# board.net
KiCad netlist of a schematic drawn in EAGLE
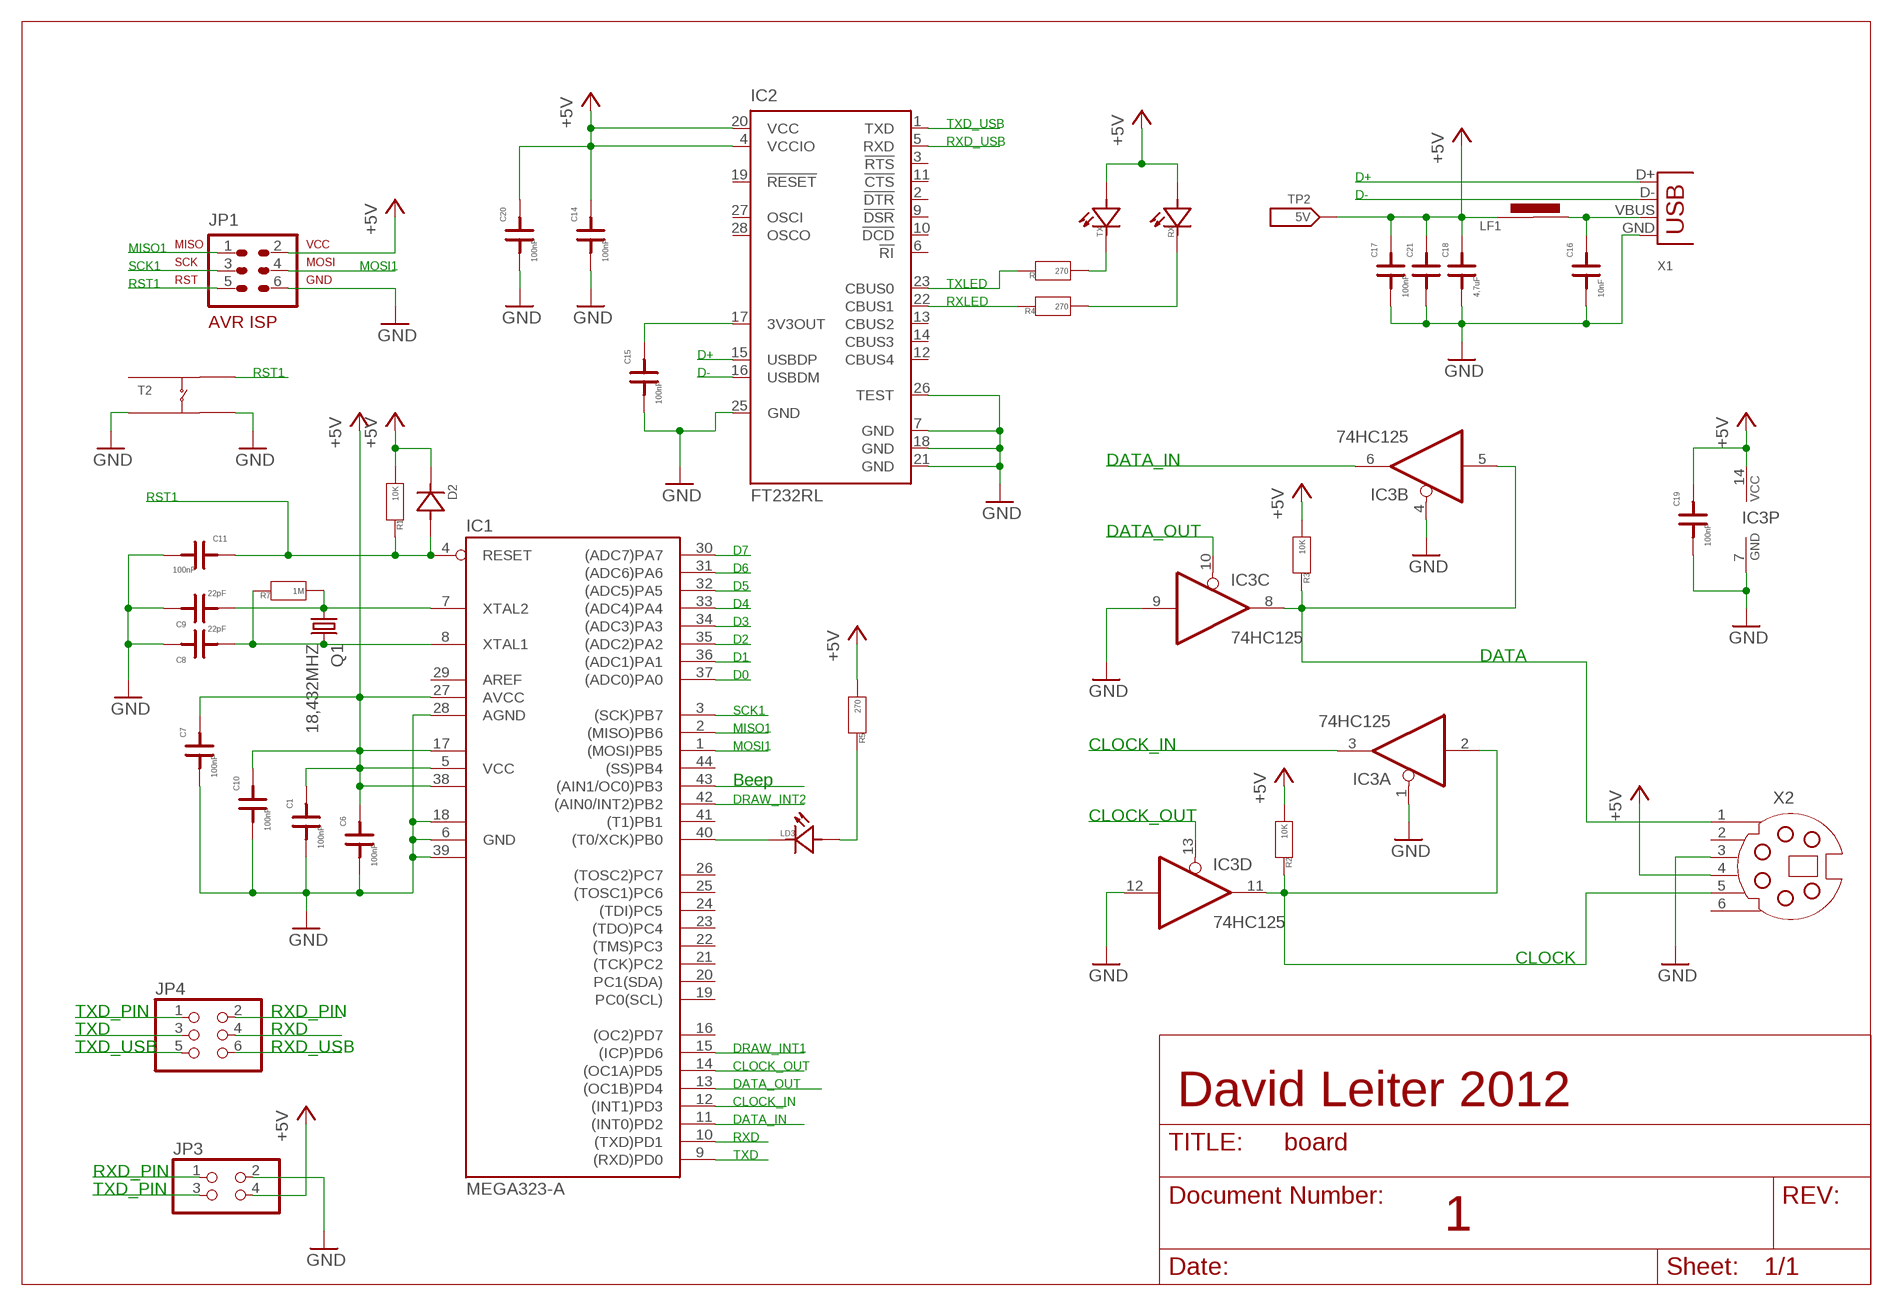
[diagram p0: schematic, sheet 1, part 1 of 2]
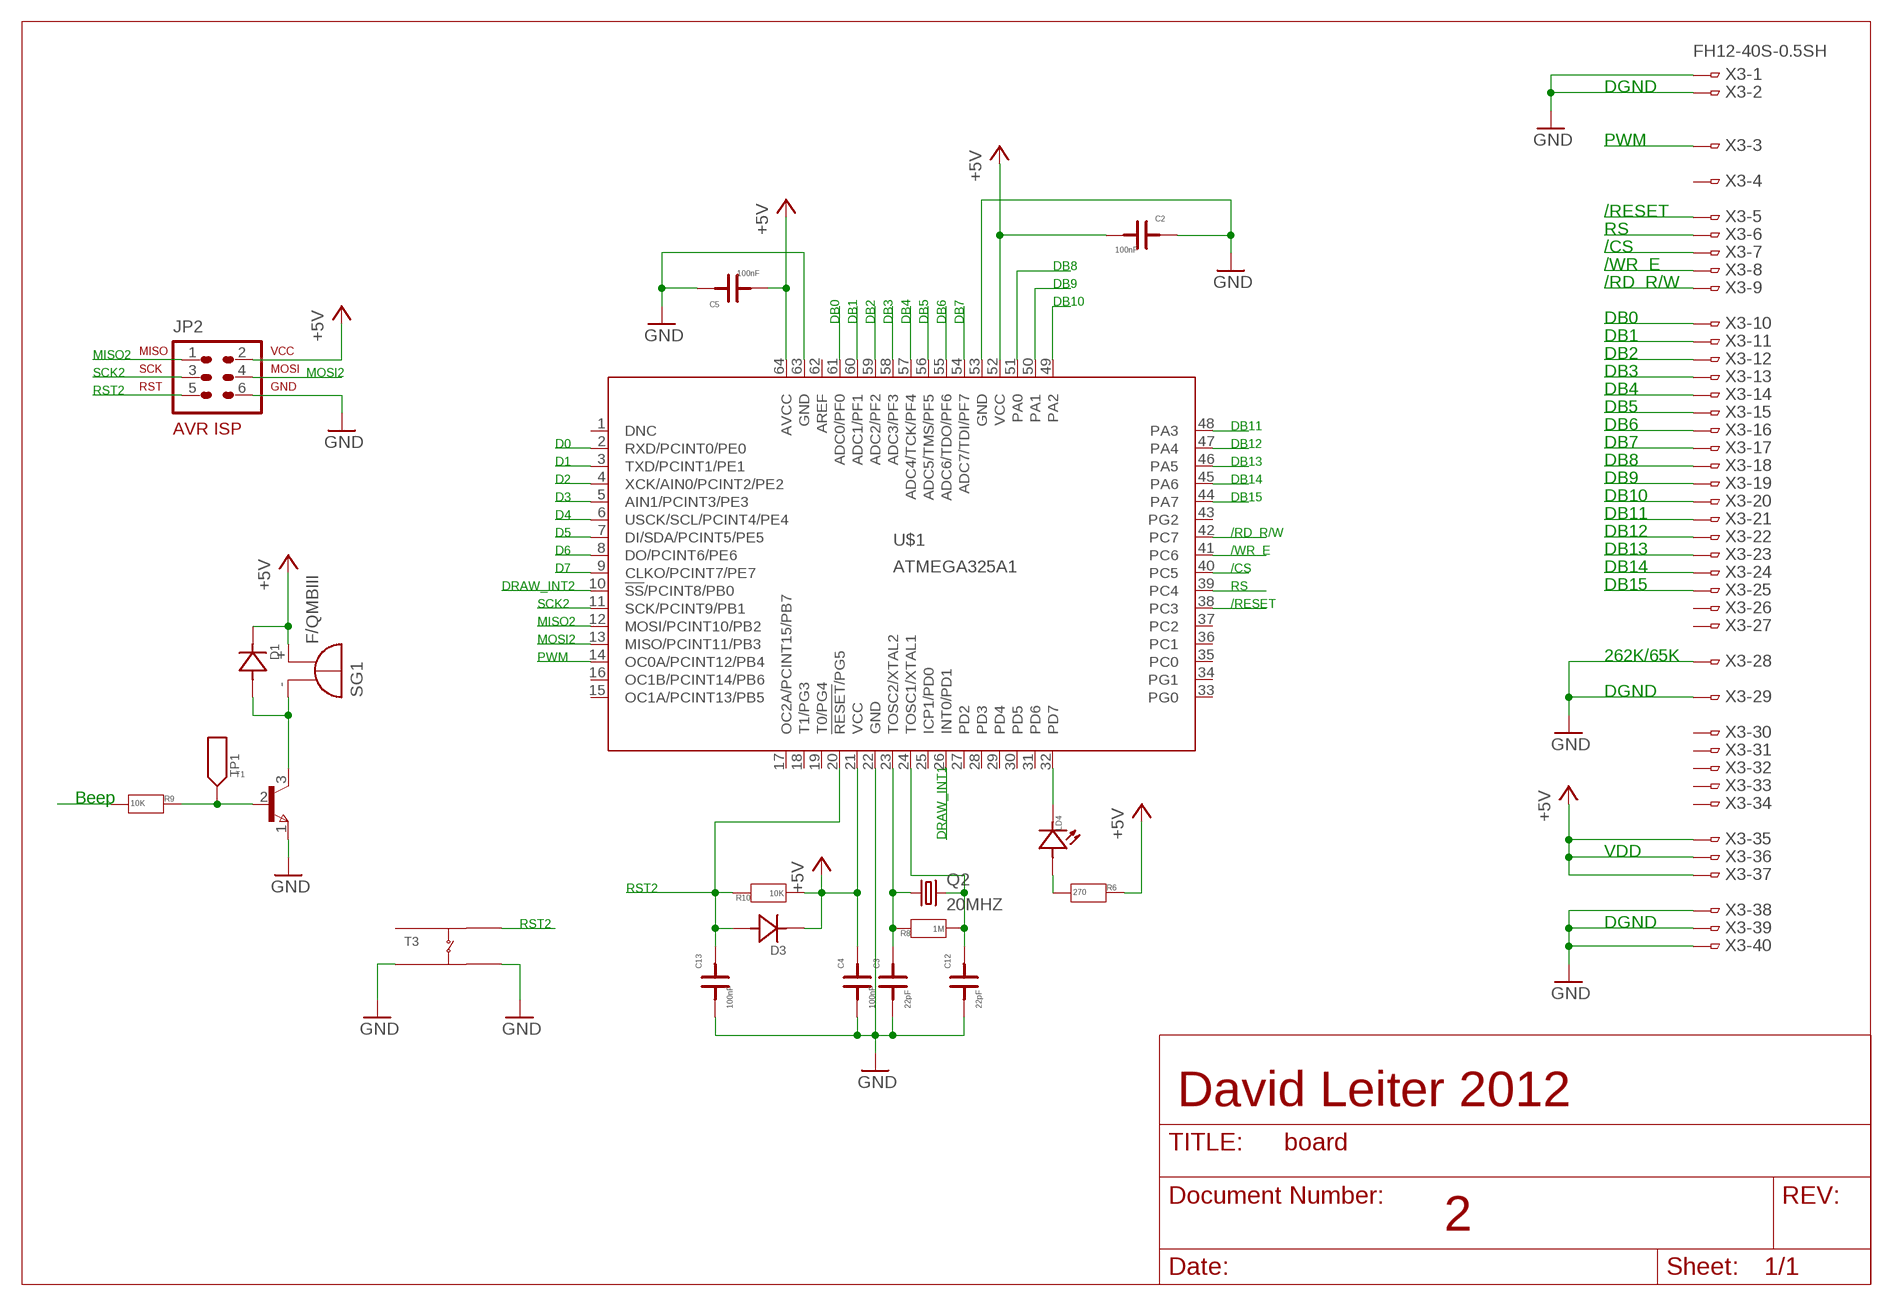
[diagram p1: schematic, sheet 1, part 2 of 2]

(export (version "E")
  (design (tool "Eeschema 10.0.6"))
  (components
    (comp (ref "C1")
      (value "100nF")
      (footprint "eagle-import:0805F")
      (libsource (lib "eagle-import") (part "C1"))
    )
    (comp (ref "C2")
      (value "100nF")
      (footprint "eagle-import:0805F")
      (libsource (lib "eagle-import") (part "C1"))
    )
    (comp (ref "C3")
      (value "22pF")
      (footprint "eagle-import:0805F")
      (libsource (lib "eagle-import") (part "C1"))
    )
    (comp (ref "C4")
      (value "100nF")
      (footprint "eagle-import:0805F")
      (libsource (lib "eagle-import") (part "C1"))
    )
    (comp (ref "C5")
      (value "100nF")
      (footprint "eagle-import:0805F")
      (libsource (lib "eagle-import") (part "C1"))
    )
    (comp (ref "C6")
      (value "100nF")
      (footprint "eagle-import:0805F")
      (libsource (lib "eagle-import") (part "C1"))
    )
    (comp (ref "C7")
      (value "100nF")
      (footprint "eagle-import:0805F")
      (libsource (lib "eagle-import") (part "C1"))
    )
    (comp (ref "C8")
      (value "22pF")
      (footprint "eagle-import:0805F")
      (libsource (lib "eagle-import") (part "C1"))
    )
    (comp (ref "C9")
      (value "22pF")
      (footprint "eagle-import:0805F")
      (libsource (lib "eagle-import") (part "C1"))
    )
    (comp (ref "C10")
      (value "100nF")
      (footprint "eagle-import:0805F")
      (libsource (lib "eagle-import") (part "C1"))
    )
    (comp (ref "C11")
      (value "100nF")
      (footprint "eagle-import:0805F")
      (libsource (lib "eagle-import") (part "C1"))
    )
    (comp (ref "C12")
      (value "22pF")
      (footprint "eagle-import:0805F")
      (libsource (lib "eagle-import") (part "C1"))
    )
    (comp (ref "C13")
      (value "100nF")
      (footprint "eagle-import:0805F")
      (libsource (lib "eagle-import") (part "C1"))
    )
    (comp (ref "C14")
      (value "100nF")
      (footprint "eagle-import:0805F")
      (libsource (lib "eagle-import") (part "C1"))
    )
    (comp (ref "C15")
      (value "100nF")
      (footprint "eagle-import:0805F")
      (libsource (lib "eagle-import") (part "C1"))
    )
    (comp (ref "C16")
      (value "10nF")
      (footprint "eagle-import:0805F")
      (libsource (lib "eagle-import") (part "C1"))
    )
    (comp (ref "C17")
      (value "100nF")
      (footprint "eagle-import:0805F")
      (libsource (lib "eagle-import") (part "C1"))
    )
    (comp (ref "C18")
      (value "4,7uF")
      (footprint "eagle-import:0805F")
      (libsource (lib "eagle-import") (part "C1"))
    )
    (comp (ref "C19")
      (value "100nF")
      (footprint "eagle-import:0805F")
      (libsource (lib "eagle-import") (part "C1"))
    )
    (comp (ref "C20")
      (value "100nF")
      (footprint "eagle-import:0805F")
      (libsource (lib "eagle-import") (part "C1"))
    )
    (comp (ref "C21")
      (value "C1")
      (footprint "eagle-import:0805F")
      (libsource (lib "eagle-import") (part "C1"))
    )
    (comp (ref "D1")
      (value "DSOD80")
      (footprint "eagle-import:SOD-80")
      (libsource (lib "eagle-import") (part "DSOD80"))
    )
    (comp (ref "D2")
      (value "DSOD80")
      (footprint "eagle-import:SOD-80")
      (libsource (lib "eagle-import") (part "DSOD80"))
    )
    (comp (ref "D3")
      (value "DSOD80")
      (footprint "eagle-import:SOD-80")
      (libsource (lib "eagle-import") (part "DSOD80"))
    )
    (comp (ref "IC1")
      (value "MEGA323-A")
      (footprint "eagle-import:TQFP44")
      (libsource (lib "eagle-import") (part "MEGA323-A"))
    )
    (comp (ref "IC2")
      (value "FT232RL")
      (footprint "eagle-import:SSOP28")
      (libsource (lib "eagle-import") (part "FT232RL"))
    )
    (comp (ref "IC3")
      (value "74HC125")
      (footprint "eagle-import:SO14")
      (libsource (lib "eagle-import") (part "74125DHCT"))
    )
    (comp (ref "JP1")
      (value "ISP1")
      (footprint "eagle-import:AVR-ISP-6")
      (libsource (lib "eagle-import") (part "AVR-ISP-6VERT"))
    )
    (comp (ref "JP2")
      (value "ISP2")
      (footprint "eagle-import:AVR-ISP-6")
      (libsource (lib "eagle-import") (part "AVR-ISP-6VERT"))
    )
    (comp (ref "JP3")
      (value "PINHD-2X2/90")
      (footprint "eagle-import:2X02_90")
      (libsource (lib "eagle-import") (part "PINHD-2X2/90"))
    )
    (comp (ref "JP4")
      (value "PINHD-2X3")
      (footprint "eagle-import:2X03")
      (libsource (lib "eagle-import") (part "PINHD-2X3"))
    )
    (comp (ref "LD3")
      (value "LEDSMD")
      (footprint "eagle-import:0805LED")
      (libsource (lib "eagle-import") (part "LEDSMD"))
    )
    (comp (ref "LD4")
      (value "LEDSMD")
      (footprint "eagle-import:0805LED")
      (libsource (lib "eagle-import") (part "LEDSMD"))
    )
    (comp (ref "LF1")
      (value "FERRIT0805")
      (footprint "eagle-import:0805")
      (libsource (lib "eagle-import") (part "FERRIT0805"))
    )
    (comp (ref "Q1")
      (value "18,432MHZ")
      (footprint "eagle-import:HC49UP")
      (libsource (lib "eagle-import") (part "CRYSTALHC49UP"))
    )
    (comp (ref "Q2")
      (value "20MHZ")
      (footprint "eagle-import:HC49UP")
      (libsource (lib "eagle-import") (part "CRYSTALHC49UP"))
    )
    (comp (ref "R")
      (value "270")
      (footprint "eagle-import:0805")
      (libsource (lib "eagle-import") (part "R1"))
    )
    (comp (ref "R1")
      (value "10K")
      (footprint "eagle-import:0805")
      (libsource (lib "eagle-import") (part "R1"))
    )
    (comp (ref "R2")
      (value "10K")
      (footprint "eagle-import:0805")
      (libsource (lib "eagle-import") (part "R1"))
    )
    (comp (ref "R3")
      (value "10K")
      (footprint "eagle-import:0805")
      (libsource (lib "eagle-import") (part "R1"))
    )
    (comp (ref "R4")
      (value "270")
      (footprint "eagle-import:0805")
      (libsource (lib "eagle-import") (part "R1"))
    )
    (comp (ref "R5")
      (value "270")
      (footprint "eagle-import:0805")
      (libsource (lib "eagle-import") (part "R1"))
    )
    (comp (ref "R6")
      (value "270")
      (footprint "eagle-import:0805")
      (libsource (lib "eagle-import") (part "R1"))
    )
    (comp (ref "R7")
      (value "1M")
      (footprint "eagle-import:0805")
      (libsource (lib "eagle-import") (part "R1"))
    )
    (comp (ref "R8")
      (value "1M")
      (footprint "eagle-import:0805")
      (libsource (lib "eagle-import") (part "R1"))
    )
    (comp (ref "R9")
      (value "10K")
      (footprint "eagle-import:0805")
      (libsource (lib "eagle-import") (part "R1"))
    )
    (comp (ref "R10")
      (value "10K")
      (footprint "eagle-import:0805")
      (libsource (lib "eagle-import") (part "R1"))
    )
    (comp (ref "RX")
      (value "LEDSMD")
      (footprint "eagle-import:0805LED")
      (libsource (lib "eagle-import") (part "LEDSMD"))
    )
    (comp (ref "SG1")
      (value "F/QMBIII")
      (footprint "eagle-import:F_QMBIII")
      (libsource (lib "eagle-import") (part "F/QMBIII"))
    )
    (comp (ref "T1")
      (value "BC817")
      (footprint "eagle-import:SOT-23")
      (libsource (lib "eagle-import") (part "BC817"))
    )
    (comp (ref "T2")
      (value "TASTERSMD")
      (footprint "eagle-import:TASTE_SMD")
      (libsource (lib "eagle-import") (part "TASTERSMD"))
    )
    (comp (ref "T3")
      (value "TASTERSMD")
      (footprint "eagle-import:TASTE_SMD")
      (libsource (lib "eagle-import") (part "TASTERSMD"))
    )
    (comp (ref "TP1")
      (value "TESTPOINT")
      (footprint "eagle-import:TESTPOINT")
      (libsource (lib "eagle-import") (part "TESTPOINT"))
    )
    (comp (ref "TP2")
      (value "5V")
      (footprint "eagle-import:TESTPOINT")
      (libsource (lib "eagle-import") (part "TESTPOINT"))
    )
    (comp (ref "TX")
      (value "LEDSMD")
      (footprint "eagle-import:0805LED")
      (libsource (lib "eagle-import") (part "LEDSMD"))
    )
    (comp (ref "U$1")
      (value "ATMEGA325A1")
      (footprint "eagle-import:TQFP64")
      (libsource (lib "eagle-import") (part "ATMEGA325A1"))
    )
    (comp (ref "X1")
      (value "USB-B-H")
      (footprint "eagle-import:USB-B-H")
      (libsource (lib "eagle-import") (part "USB-B-H"))
    )
    (comp (ref "X2")
      (value "SSV-G06")
      (footprint "eagle-import:SSV-BC06")
      (libsource (lib "eagle-import") (part "SSV-G06"))
    )
    (comp (ref "X3")
      (value "FH12-40S-0.5SH")
      (footprint "eagle-import:FH12-40S-0.5SH")
      (fields (field (name "MPN") "FH12-40S-0.5SH(55)"))
      (libsource (lib "eagle-import") (part "FH12-40S-0.5SH"))
    )
  )
  (nets
    (net (code "1") (name "+5V") (class "Default")
      (node (ref "C1") (pin "2") (pinfunction "2_2") (pintype "bidirectional"))
      (node (ref "C10") (pin "2") (pinfunction "2_2") (pintype "bidirectional"))
      (node (ref "C14") (pin "2") (pinfunction "2_2") (pintype "bidirectional"))
      (node (ref "C17") (pin "2") (pinfunction "2_2") (pintype "bidirectional"))
      (node (ref "C18") (pin "2") (pinfunction "2_2") (pintype "bidirectional"))
      (node (ref "C19") (pin "2") (pinfunction "2_2") (pintype "bidirectional"))
      (node (ref "C2") (pin "1") (pinfunction "1_1") (pintype "bidirectional"))
      (node (ref "C20") (pin "2") (pinfunction "2_2") (pintype "bidirectional"))
      (node (ref "C21") (pin "2") (pinfunction "2_2") (pintype "bidirectional"))
      (node (ref "C4") (pin "2") (pinfunction "2_2") (pintype "bidirectional"))
      (node (ref "C5") (pin "1") (pinfunction "1_1") (pintype "bidirectional"))
      (node (ref "C6") (pin "2") (pinfunction "2_2") (pintype "bidirectional"))
      (node (ref "C7") (pin "2") (pinfunction "2_2") (pintype "bidirectional"))
      (node (ref "D1") (pin "1") (pinfunction "K_1") (pintype "bidirectional"))
      (node (ref "D2") (pin "1") (pinfunction "K_1") (pintype "bidirectional"))
      (node (ref "D3") (pin "1") (pinfunction "K_1") (pintype "bidirectional"))
      (node (ref "IC1") (pin "17") (pinfunction "VCC1_17") (pintype "power_in"))
      (node (ref "IC1") (pin "27") (pinfunction "AVCC_27") (pintype "power_in"))
      (node (ref "IC1") (pin "38") (pinfunction "VCC2_38") (pintype "power_in"))
      (node (ref "IC1") (pin "5") (pinfunction "VCC_5") (pintype "power_in"))
      (node (ref "IC2") (pin "20") (pinfunction "VCC_20") (pintype "power_in"))
      (node (ref "IC2") (pin "4") (pinfunction "VCCIO_4") (pintype "power_in"))
      (node (ref "IC3") (pin "14") (pinfunction "VCC_14") (pintype "power_in"))
      (node (ref "JP1") (pin "2") (pinfunction "2_2") (pintype "passive"))
      (node (ref "JP2") (pin "2") (pinfunction "2_2") (pintype "passive"))
      (node (ref "JP3") (pin "4") (pinfunction "4_4") (pintype "passive"))
      (node (ref "LF1") (pin "1") (pinfunction "1_1") (pintype "bidirectional"))
      (node (ref "R1") (pin "1") (pinfunction "1_1") (pintype "bidirectional"))
      (node (ref "R10") (pin "1") (pinfunction "1_1") (pintype "bidirectional"))
      (node (ref "R2") (pin "1") (pinfunction "1_1") (pintype "bidirectional"))
      (node (ref "R3") (pin "1") (pinfunction "1_1") (pintype "bidirectional"))
      (node (ref "R5") (pin "1") (pinfunction "1_1") (pintype "bidirectional"))
      (node (ref "R6") (pin "2") (pinfunction "2_2") (pintype "bidirectional"))
      (node (ref "RX") (pin "A") (pinfunction "2_A") (pintype "bidirectional"))
      (node (ref "SG1") (pin "+") (pinfunction "-_+") (pintype "passive"))
      (node (ref "TP2") (pin "P$1") (pinfunction "TP_P$1") (pintype "bidirectional"))
      (node (ref "TX") (pin "A") (pinfunction "2_A") (pintype "bidirectional"))
      (node (ref "U$1") (pin "21") (pinfunction "VCC_21") (pintype "power_in"))
      (node (ref "U$1") (pin "52") (pinfunction "VCC_52") (pintype "power_in"))
      (node (ref "U$1") (pin "64") (pinfunction "AVCC_64") (pintype "power_in"))
      (node (ref "X2") (pin "4") (pinfunction "4_4") (pintype "passive"))
      (node (ref "X3") (pin "35") (pinfunction "1_35") (pintype "passive"))
      (node (ref "X3") (pin "36") (pinfunction "1_36") (pintype "passive"))
      (node (ref "X3") (pin "37") (pinfunction "1_37") (pintype "passive"))
    )
    (net (code "2") (name "/BEEP") (class "Default")
      (node (ref "IC1") (pin "43") (pinfunction "(AIN1/OC0)PB3_43") (pintype "bidirectional"))
      (node (ref "R9") (pin "1") (pinfunction "1_1") (pintype "bidirectional"))
    )
    (net (code "3") (name "/CLOCK_IN") (class "Default")
      (node (ref "IC1") (pin "12") (pinfunction "(INT1)PD3_12") (pintype "bidirectional"))
      (node (ref "IC3") (pin "3") (pinfunction "O_3") (pintype "tri_state"))
    )
    (net (code "4") (name "/CLOCK_OUT") (class "Default")
      (node (ref "IC1") (pin "14") (pinfunction "(OC1A)PD5_14") (pintype "bidirectional"))
      (node (ref "IC3") (pin "13") (pinfunction "OE_13") (pintype "input"))
    )
    (net (code "5") (name "/D+") (class "Default")
      (node (ref "IC2") (pin "15") (pinfunction "USBDP_15") (pintype "bidirectional"))
      (node (ref "X1") (pin "D+") (pinfunction "D+_D+") (pintype "bidirectional"))
    )
    (net (code "6") (name "/D-") (class "Default")
      (node (ref "IC2") (pin "16") (pinfunction "USBDM_16") (pintype "bidirectional"))
      (node (ref "X1") (pin "D-") (pinfunction "D-_D-") (pintype "bidirectional"))
    )
    (net (code "7") (name "/D0") (class "Default")
      (node (ref "IC1") (pin "37") (pinfunction "(ADC0)PA0_37") (pintype "bidirectional"))
      (node (ref "U$1") (pin "2") (pinfunction "RXD/PCINT0/PE0_2") (pintype "bidirectional"))
    )
    (net (code "8") (name "/D1") (class "Default")
      (node (ref "IC1") (pin "36") (pinfunction "(ADC1)PA1_36") (pintype "bidirectional"))
      (node (ref "U$1") (pin "3") (pinfunction "TXD/PCINT1/PE1_3") (pintype "bidirectional"))
    )
    (net (code "9") (name "/D2") (class "Default")
      (node (ref "IC1") (pin "35") (pinfunction "(ADC2)PA2_35") (pintype "bidirectional"))
      (node (ref "U$1") (pin "4") (pinfunction "XCK/AIN0/PCINT2/PE2_4") (pintype "bidirectional"))
    )
    (net (code "10") (name "/D3") (class "Default")
      (node (ref "IC1") (pin "34") (pinfunction "(ADC3)PA3_34") (pintype "bidirectional"))
      (node (ref "U$1") (pin "5") (pinfunction "AIN1/PCINT3/PE3_5") (pintype "bidirectional"))
    )
    (net (code "11") (name "/D4") (class "Default")
      (node (ref "IC1") (pin "33") (pinfunction "(ADC4)PA4_33") (pintype "bidirectional"))
      (node (ref "U$1") (pin "6") (pinfunction "USCK/SCL/PCINT4/PE4_6") (pintype "bidirectional"))
    )
    (net (code "12") (name "/D5") (class "Default")
      (node (ref "IC1") (pin "32") (pinfunction "(ADC5)PA5_32") (pintype "bidirectional"))
      (node (ref "U$1") (pin "7") (pinfunction "DI/SDA/PCINT5/PE5_7") (pintype "bidirectional"))
    )
    (net (code "13") (name "/D6") (class "Default")
      (node (ref "IC1") (pin "31") (pinfunction "(ADC6)PA6_31") (pintype "bidirectional"))
      (node (ref "U$1") (pin "8") (pinfunction "DO/PCINT6/PE6_8") (pintype "bidirectional"))
    )
    (net (code "14") (name "/D7") (class "Default")
      (node (ref "IC1") (pin "30") (pinfunction "(ADC7)PA7_30") (pintype "bidirectional"))
      (node (ref "U$1") (pin "9") (pinfunction "CLKO/PCINT7/PE7_9") (pintype "bidirectional"))
    )
    (net (code "15") (name "/DATA_IN") (class "Default")
      (node (ref "IC1") (pin "11") (pinfunction "(INT0)PD2_11") (pintype "bidirectional"))
      (node (ref "IC3") (pin "6") (pinfunction "O_6") (pintype "tri_state"))
    )
    (net (code "16") (name "/DATA_OUT") (class "Default")
      (node (ref "IC1") (pin "13") (pinfunction "(OC1B)PD4_13") (pintype "bidirectional"))
      (node (ref "IC3") (pin "10") (pinfunction "OE_10") (pintype "input"))
    )
    (net (code "17") (name "/DB0") (class "Default")
      (node (ref "U$1") (pin "61") (pinfunction "ADC0/PF0_61") (pintype "bidirectional"))
      (node (ref "X3") (pin "10") (pinfunction "1_10") (pintype "passive"))
    )
    (net (code "18") (name "/DB1") (class "Default")
      (node (ref "U$1") (pin "60") (pinfunction "ADC1/PF1_60") (pintype "bidirectional"))
      (node (ref "X3") (pin "11") (pinfunction "1_11") (pintype "passive"))
    )
    (net (code "19") (name "/DB2") (class "Default")
      (node (ref "U$1") (pin "59") (pinfunction "ADC2/PF2_59") (pintype "bidirectional"))
      (node (ref "X3") (pin "12") (pinfunction "1_12") (pintype "passive"))
    )
    (net (code "20") (name "/DB3") (class "Default")
      (node (ref "U$1") (pin "58") (pinfunction "ADC3/PF3_58") (pintype "bidirectional"))
      (node (ref "X3") (pin "13") (pinfunction "1_13") (pintype "passive"))
    )
    (net (code "21") (name "/DB4") (class "Default")
      (node (ref "U$1") (pin "57") (pinfunction "ADC4/TCK/PF4_57") (pintype "bidirectional"))
      (node (ref "X3") (pin "14") (pinfunction "1_14") (pintype "passive"))
    )
    (net (code "22") (name "/DB5") (class "Default")
      (node (ref "U$1") (pin "56") (pinfunction "ADC5/TMS/PF5_56") (pintype "bidirectional"))
      (node (ref "X3") (pin "15") (pinfunction "1_15") (pintype "passive"))
    )
    (net (code "23") (name "/DB6") (class "Default")
      (node (ref "U$1") (pin "55") (pinfunction "ADC6/TDO/PF6_55") (pintype "bidirectional"))
      (node (ref "X3") (pin "16") (pinfunction "1_16") (pintype "passive"))
    )
    (net (code "24") (name "/DB7") (class "Default")
      (node (ref "U$1") (pin "54") (pinfunction "ADC7/TDI/PF7_54") (pintype "bidirectional"))
      (node (ref "X3") (pin "17") (pinfunction "1_17") (pintype "passive"))
    )
    (net (code "25") (name "/DB8") (class "Default")
      (node (ref "U$1") (pin "51") (pinfunction "PA0_51") (pintype "bidirectional"))
      (node (ref "X3") (pin "18") (pinfunction "1_18") (pintype "passive"))
    )
    (net (code "26") (name "/DB9") (class "Default")
      (node (ref "U$1") (pin "50") (pinfunction "PA1_50") (pintype "bidirectional"))
      (node (ref "X3") (pin "19") (pinfunction "1_19") (pintype "passive"))
    )
    (net (code "27") (name "/DB10") (class "Default")
      (node (ref "U$1") (pin "49") (pinfunction "PA2_49") (pintype "bidirectional"))
      (node (ref "X3") (pin "20") (pinfunction "1_20") (pintype "passive"))
    )
    (net (code "28") (name "/DB11") (class "Default")
      (node (ref "U$1") (pin "48") (pinfunction "PA3_48") (pintype "bidirectional"))
      (node (ref "X3") (pin "21") (pinfunction "1_21") (pintype "passive"))
    )
    (net (code "29") (name "/DB12") (class "Default")
      (node (ref "U$1") (pin "47") (pinfunction "PA4_47") (pintype "bidirectional"))
      (node (ref "X3") (pin "22") (pinfunction "1_22") (pintype "passive"))
    )
    (net (code "30") (name "/DB13") (class "Default")
      (node (ref "U$1") (pin "46") (pinfunction "PA5_46") (pintype "bidirectional"))
      (node (ref "X3") (pin "23") (pinfunction "1_23") (pintype "passive"))
    )
    (net (code "31") (name "/DB14") (class "Default")
      (node (ref "U$1") (pin "45") (pinfunction "PA6_45") (pintype "bidirectional"))
      (node (ref "X3") (pin "24") (pinfunction "1_24") (pintype "passive"))
    )
    (net (code "32") (name "/DB15") (class "Default")
      (node (ref "U$1") (pin "44") (pinfunction "PA7_44") (pintype "bidirectional"))
      (node (ref "X3") (pin "25") (pinfunction "1_25") (pintype "passive"))
    )
    (net (code "33") (name "/DRAW_INT1") (class "Default")
      (node (ref "IC1") (pin "15") (pinfunction "(ICP)PD6_15") (pintype "bidirectional"))
      (node (ref "U$1") (pin "26") (pinfunction "INT0/PD1_26") (pintype "bidirectional"))
    )
    (net (code "34") (name "/DRAW_INT2") (class "Default")
      (node (ref "IC1") (pin "42") (pinfunction "(AIN0/INT2)PB2_42") (pintype "bidirectional"))
      (node (ref "U$1") (pin "10") (pinfunction "~{SS}/PCINT8/PB0_10") (pintype "bidirectional"))
    )
    (net (code "35") (name "/MISO1") (class "Default")
      (node (ref "IC1") (pin "2") (pinfunction "(MISO)PB6_2") (pintype "bidirectional"))
      (node (ref "JP1") (pin "1") (pinfunction "1_1") (pintype "passive"))
    )
    (net (code "36") (name "/MISO2") (class "Default")
      (node (ref "JP2") (pin "1") (pinfunction "1_1") (pintype "passive"))
      (node (ref "U$1") (pin "13") (pinfunction "MISO/PCINT11/PB3_13") (pintype "bidirectional"))
    )
    (net (code "37") (name "/MOSI1") (class "Default")
      (node (ref "IC1") (pin "1") (pinfunction "(MOSI)PB5_1") (pintype "bidirectional"))
      (node (ref "JP1") (pin "4") (pinfunction "4_4") (pintype "passive"))
    )
    (net (code "38") (name "/MOSI2") (class "Default")
      (node (ref "JP2") (pin "4") (pinfunction "4_4") (pintype "passive"))
      (node (ref "U$1") (pin "12") (pinfunction "MOSI/PCINT10/PB2_12") (pintype "bidirectional"))
    )
    (net (code "39") (name "/PWM") (class "Default")
      (node (ref "U$1") (pin "14") (pinfunction "OC0A/PCINT12/PB4_14") (pintype "bidirectional"))
      (node (ref "X3") (pin "3") (pinfunction "1_3") (pintype "passive"))
    )
    (net (code "40") (name "/RS") (class "Default")
      (node (ref "U$1") (pin "39") (pinfunction "PC4_39") (pintype "bidirectional"))
      (node (ref "X3") (pin "6") (pinfunction "1_6") (pintype "passive"))
    )
    (net (code "41") (name "/RST1") (class "Default")
      (node (ref "C11") (pin "2") (pinfunction "2_2") (pintype "bidirectional"))
      (node (ref "D2") (pin "2") (pinfunction "A_2") (pintype "bidirectional"))
      (node (ref "IC1") (pin "4") (pinfunction "RESET_4") (pintype "input"))
      (node (ref "JP1") (pin "5") (pinfunction "5_5") (pintype "passive"))
      (node (ref "R1") (pin "2") (pinfunction "2_2") (pintype "bidirectional"))
      (node (ref "T2") (pin "A2") (pinfunction "A2_A2") (pintype "bidirectional"))
    )
    (net (code "42") (name "/RST2") (class "Default")
      (node (ref "C13") (pin "2") (pinfunction "2_2") (pintype "bidirectional"))
      (node (ref "D3") (pin "2") (pinfunction "A_2") (pintype "bidirectional"))
      (node (ref "JP2") (pin "5") (pinfunction "5_5") (pintype "passive"))
      (node (ref "R10") (pin "2") (pinfunction "2_2") (pintype "bidirectional"))
      (node (ref "T3") (pin "A2") (pinfunction "A2_A2") (pintype "bidirectional"))
      (node (ref "U$1") (pin "20") (pinfunction "~{RESET}/PG5_20") (pintype "input"))
    )
    (net (code "43") (name "/RXD") (class "Default")
      (node (ref "IC1") (pin "10") (pinfunction "(TXD)PD1_10") (pintype "bidirectional"))
      (node (ref "JP4") (pin "4") (pinfunction "4_4") (pintype "passive"))
    )
    (net (code "44") (name "/RXD_PIN") (class "Default")
      (node (ref "JP3") (pin "1") (pinfunction "1_1") (pintype "passive"))
      (node (ref "JP4") (pin "2") (pinfunction "2_2") (pintype "passive"))
    )
    (net (code "45") (name "/RXD_USB") (class "Default")
      (node (ref "IC2") (pin "5") (pinfunction "RXD_5") (pintype "input"))
      (node (ref "JP4") (pin "6") (pinfunction "6_6") (pintype "passive"))
    )
    (net (code "46") (name "/SCK1") (class "Default")
      (node (ref "IC1") (pin "3") (pinfunction "(SCK)PB7_3") (pintype "bidirectional"))
      (node (ref "JP1") (pin "3") (pinfunction "3_3") (pintype "passive"))
    )
    (net (code "47") (name "/SCK2") (class "Default")
      (node (ref "JP2") (pin "3") (pinfunction "3_3") (pintype "passive"))
      (node (ref "U$1") (pin "11") (pinfunction "SCK/PCINT9/PB1_11") (pintype "bidirectional"))
    )
    (net (code "48") (name "/TXD") (class "Default")
      (node (ref "IC1") (pin "9") (pinfunction "(RXD)PD0_9") (pintype "bidirectional"))
      (node (ref "JP4") (pin "3") (pinfunction "3_3") (pintype "passive"))
    )
    (net (code "49") (name "/TXD_PIN") (class "Default")
      (node (ref "JP3") (pin "3") (pinfunction "3_3") (pintype "passive"))
      (node (ref "JP4") (pin "1") (pinfunction "1_1") (pintype "passive"))
    )
    (net (code "50") (name "/TXD_USB") (class "Default")
      (node (ref "IC2") (pin "1") (pinfunction "TXD_1") (pintype "output"))
      (node (ref "JP4") (pin "5") (pinfunction "5_5") (pintype "passive"))
    )
    (net (code "51") (name "/{slash}CS") (class "Default")
      (node (ref "U$1") (pin "40") (pinfunction "PC5_40") (pintype "bidirectional"))
      (node (ref "X3") (pin "7") (pinfunction "1_7") (pintype "passive"))
    )
    (net (code "52") (name "/{slash}RD") (class "Default")
      (node (ref "U$1") (pin "42") (pinfunction "PC7_42") (pintype "bidirectional"))
      (node (ref "X3") (pin "9") (pinfunction "1_9") (pintype "passive"))
    )
    (net (code "53") (name "/{slash}RESET") (class "Default")
      (node (ref "U$1") (pin "38") (pinfunction "PC3_38") (pintype "bidirectional"))
      (node (ref "X3") (pin "5") (pinfunction "1_5") (pintype "passive"))
    )
    (net (code "54") (name "/{slash}WR") (class "Default")
      (node (ref "U$1") (pin "41") (pinfunction "PC6_41") (pintype "bidirectional"))
      (node (ref "X3") (pin "8") (pinfunction "1_8") (pintype "passive"))
    )
    (net (code "55") (name "GND") (class "Default")
      (node (ref "C1") (pin "1") (pinfunction "1_1") (pintype "bidirectional"))
      (node (ref "C10") (pin "1") (pinfunction "1_1") (pintype "bidirectional"))
      (node (ref "C11") (pin "1") (pinfunction "1_1") (pintype "bidirectional"))
      (node (ref "C12") (pin "1") (pinfunction "1_1") (pintype "bidirectional"))
      (node (ref "C13") (pin "1") (pinfunction "1_1") (pintype "bidirectional"))
      (node (ref "C14") (pin "1") (pinfunction "1_1") (pintype "bidirectional"))
      (node (ref "C15") (pin "1") (pinfunction "1_1") (pintype "bidirectional"))
      (node (ref "C16") (pin "1") (pinfunction "1_1") (pintype "bidirectional"))
      (node (ref "C17") (pin "1") (pinfunction "1_1") (pintype "bidirectional"))
      (node (ref "C18") (pin "1") (pinfunction "1_1") (pintype "bidirectional"))
      (node (ref "C19") (pin "1") (pinfunction "1_1") (pintype "bidirectional"))
      (node (ref "C2") (pin "2") (pinfunction "2_2") (pintype "bidirectional"))
      (node (ref "C20") (pin "1") (pinfunction "1_1") (pintype "bidirectional"))
      (node (ref "C21") (pin "1") (pinfunction "1_1") (pintype "bidirectional"))
      (node (ref "C3") (pin "1") (pinfunction "1_1") (pintype "bidirectional"))
      (node (ref "C4") (pin "1") (pinfunction "1_1") (pintype "bidirectional"))
      (node (ref "C5") (pin "2") (pinfunction "2_2") (pintype "bidirectional"))
      (node (ref "C6") (pin "1") (pinfunction "1_1") (pintype "bidirectional"))
      (node (ref "C7") (pin "1") (pinfunction "1_1") (pintype "bidirectional"))
      (node (ref "C8") (pin "2") (pinfunction "2_2") (pintype "bidirectional"))
      (node (ref "C9") (pin "2") (pinfunction "2_2") (pintype "bidirectional"))
      (node (ref "IC1") (pin "18") (pinfunction "GND1_18") (pintype "power_in"))
      (node (ref "IC1") (pin "28") (pinfunction "AGND_28") (pintype "power_in"))
      (node (ref "IC1") (pin "39") (pinfunction "GND2_39") (pintype "power_in"))
      (node (ref "IC1") (pin "6") (pinfunction "GND_6") (pintype "power_in"))
      (node (ref "IC2") (pin "18") (pinfunction "GND_18") (pintype "power_in"))
      (node (ref "IC2") (pin "21") (pinfunction "GND_21") (pintype "power_in"))
      (node (ref "IC2") (pin "25") (pinfunction "GND_25") (pintype "power_in"))
      (node (ref "IC2") (pin "26") (pinfunction "TEST_26") (pintype "input"))
      (node (ref "IC2") (pin "7") (pinfunction "GND_7") (pintype "power_in"))
      (node (ref "IC3") (pin "1") (pinfunction "OE_1") (pintype "input"))
      (node (ref "IC3") (pin "12") (pinfunction "I_12") (pintype "input"))
      (node (ref "IC3") (pin "4") (pinfunction "OE_4") (pintype "input"))
      (node (ref "IC3") (pin "7") (pinfunction "GND_7") (pintype "power_in"))
      (node (ref "IC3") (pin "9") (pinfunction "I_9") (pintype "input"))
      (node (ref "JP1") (pin "6") (pinfunction "6_6") (pintype "passive"))
      (node (ref "JP2") (pin "6") (pinfunction "6_6") (pintype "passive"))
      (node (ref "JP3") (pin "2") (pinfunction "2_2") (pintype "passive"))
      (node (ref "T1") (pin "1") (pinfunction "E_1") (pintype "passive"))
      (node (ref "T2") (pin "B1") (pinfunction "B1_B1") (pintype "bidirectional"))
      (node (ref "T2") (pin "B2") (pinfunction "B2_B2") (pintype "bidirectional"))
      (node (ref "T3") (pin "B1") (pinfunction "B1_B1") (pintype "bidirectional"))
      (node (ref "T3") (pin "B2") (pinfunction "B2_B2") (pintype "bidirectional"))
      (node (ref "U$1") (pin "22") (pinfunction "GND_22") (pintype "power_in"))
      (node (ref "U$1") (pin "53") (pinfunction "GND_53") (pintype "power_in"))
      (node (ref "U$1") (pin "63") (pinfunction "GND_63") (pintype "power_in"))
      (node (ref "X1") (pin "GND") (pinfunction "GND_GND") (pintype "bidirectional"))
      (node (ref "X2") (pin "3") (pinfunction "3_3") (pintype "passive"))
      (node (ref "X3") (pin "1") (pinfunction "1_1") (pintype "passive"))
      (node (ref "X3") (pin "2") (pinfunction "1_2") (pintype "passive"))
      (node (ref "X3") (pin "28") (pinfunction "1_28") (pintype "passive"))
      (node (ref "X3") (pin "29") (pinfunction "1_29") (pintype "passive"))
      (node (ref "X3") (pin "38") (pinfunction "1_38") (pintype "passive"))
      (node (ref "X3") (pin "39") (pinfunction "1_39") (pintype "passive"))
      (node (ref "X3") (pin "40") (pinfunction "1_40") (pintype "passive"))
    )
    (net (code "56") (name "Net-(C16-Pad2)") (class "Default")
      (node (ref "C16") (pin "2") (pinfunction "2_2") (pintype "bidirectional"))
      (node (ref "LF1") (pin "2") (pinfunction "2_2") (pintype "bidirectional"))
      (node (ref "X1") (pin "VBUS") (pinfunction "VBUS_VBUS") (pintype "bidirectional"))
    )
    (net (code "57") (name "Net-(D1-A)") (class "Default")
      (node (ref "D1") (pin "2") (pinfunction "A_2") (pintype "bidirectional"))
      (node (ref "SG1") (pin "-") (pinfunction "+_-") (pintype "passive"))
      (node (ref "T1") (pin "3") (pinfunction "C_3") (pintype "passive"))
    )
    (net (code "58") (name "Net-(IC1-(T0{slash}XCK)PB0)") (class "Default")
      (node (ref "IC1") (pin "40") (pinfunction "(T0/XCK)PB0_40") (pintype "bidirectional"))
      (node (ref "LD3") (pin "K") (pinfunction "1_K") (pintype "bidirectional"))
    )
    (net (code "59") (name "Net-(IC1-XTAL1)") (class "Default")
      (node (ref "C8") (pin "1") (pinfunction "1_1") (pintype "bidirectional"))
      (node (ref "IC1") (pin "8") (pinfunction "XTAL1_8") (pintype "bidirectional"))
      (node (ref "Q1") (pin "2") (pinfunction "2_2") (pintype "passive"))
      (node (ref "R7") (pin "2") (pinfunction "2_2") (pintype "bidirectional"))
    )
    (net (code "60") (name "Net-(IC1-XTAL2)") (class "Default")
      (node (ref "C9") (pin "1") (pinfunction "1_1") (pintype "bidirectional"))
      (node (ref "IC1") (pin "7") (pinfunction "XTAL2_7") (pintype "bidirectional"))
      (node (ref "Q1") (pin "1") (pinfunction "1_1") (pintype "passive"))
      (node (ref "R7") (pin "1") (pinfunction "1_1") (pintype "bidirectional"))
    )
    (net (code "61") (name "Net-(IC2-3V3OUT)") (class "Default")
      (node (ref "C15") (pin "2") (pinfunction "2_2") (pintype "bidirectional"))
      (node (ref "IC2") (pin "17") (pinfunction "3V3OUT_17") (pintype "output"))
    )
    (net (code "62") (name "Net-(IC2-CBUS0)") (class "Default")
      (node (ref "IC2") (pin "23") (pinfunction "CBUS0_23") (pintype "bidirectional"))
      (node (ref "R") (pin "2") (pinfunction "2_2") (pintype "bidirectional"))
    )
    (net (code "63") (name "Net-(IC2-CBUS1)") (class "Default")
      (node (ref "IC2") (pin "22") (pinfunction "CBUS1_22") (pintype "bidirectional"))
      (node (ref "R4") (pin "2") (pinfunction "2_2") (pintype "bidirectional"))
    )
    (net (code "64") (name "Net-(IC3A-I)") (class "Default")
      (node (ref "IC3") (pin "11") (pinfunction "O_11") (pintype "tri_state"))
      (node (ref "IC3") (pin "2") (pinfunction "I_2") (pintype "input"))
      (node (ref "R2") (pin "2") (pinfunction "2_2") (pintype "bidirectional"))
      (node (ref "X2") (pin "5") (pinfunction "5_5") (pintype "passive"))
    )
    (net (code "65") (name "Net-(IC3B-I)") (class "Default")
      (node (ref "IC3") (pin "5") (pinfunction "I_5") (pintype "input"))
      (node (ref "IC3") (pin "8") (pinfunction "O_8") (pintype "tri_state"))
      (node (ref "R3") (pin "2") (pinfunction "2_2") (pintype "bidirectional"))
      (node (ref "X2") (pin "1") (pinfunction "1_1") (pintype "passive"))
    )
    (net (code "66") (name "Net-(LD3-2)") (class "Default")
      (node (ref "LD3") (pin "A") (pinfunction "2_A") (pintype "bidirectional"))
      (node (ref "R5") (pin "2") (pinfunction "2_2") (pintype "bidirectional"))
    )
    (net (code "67") (name "Net-(LD4-1)") (class "Default")
      (node (ref "LD4") (pin "K") (pinfunction "1_K") (pintype "bidirectional"))
      (node (ref "U$1") (pin "32") (pinfunction "PD7_32") (pintype "bidirectional"))
    )
    (net (code "68") (name "Net-(LD4-2)") (class "Default")
      (node (ref "LD4") (pin "A") (pinfunction "2_A") (pintype "bidirectional"))
      (node (ref "R6") (pin "1") (pinfunction "1_1") (pintype "bidirectional"))
    )
    (net (code "69") (name "Net-(RX-1)") (class "Default")
      (node (ref "R4") (pin "1") (pinfunction "1_1") (pintype "bidirectional"))
      (node (ref "RX") (pin "K") (pinfunction "1_K") (pintype "bidirectional"))
    )
    (net (code "70") (name "Net-(T1-B)") (class "Default")
      (node (ref "R9") (pin "2") (pinfunction "2_2") (pintype "bidirectional"))
      (node (ref "T1") (pin "2") (pinfunction "B_2") (pintype "passive"))
      (node (ref "TP1") (pin "P$1") (pinfunction "TP_P$1") (pintype "bidirectional"))
    )
    (net (code "71") (name "Net-(TX-1)") (class "Default")
      (node (ref "R") (pin "1") (pinfunction "1_1") (pintype "bidirectional"))
      (node (ref "TX") (pin "K") (pinfunction "1_K") (pintype "bidirectional"))
    )
    (net (code "72") (name "Net-(U$1-TOSC1{slash}XTAL1)") (class "Default")
      (node (ref "C12") (pin "2") (pinfunction "2_2") (pintype "bidirectional"))
      (node (ref "Q2") (pin "2") (pinfunction "2_2") (pintype "passive"))
      (node (ref "R8") (pin "1") (pinfunction "1_1") (pintype "bidirectional"))
      (node (ref "U$1") (pin "24") (pinfunction "TOSC1/XTAL1_24") (pintype "input"))
    )
    (net (code "73") (name "Net-(U$1-TOSC2{slash}XTAL2)") (class "Default")
      (node (ref "C3") (pin "2") (pinfunction "2_2") (pintype "bidirectional"))
      (node (ref "Q2") (pin "1") (pinfunction "1_1") (pintype "passive"))
      (node (ref "R8") (pin "2") (pinfunction "2_2") (pintype "bidirectional"))
      (node (ref "U$1") (pin "23") (pinfunction "TOSC2/XTAL2_23") (pintype "output"))
    )
    (net (code "74") (name "unconnected-(IC1-(OC2)PD7-Pad16)") (class "Default")
      (node (ref "IC1") (pin "16") (pinfunction "(OC2)PD7_16") (pintype "bidirectional"))
    )
    (net (code "75") (name "unconnected-(IC1-(SS)PB4-Pad44)") (class "Default")
      (node (ref "IC1") (pin "44") (pinfunction "(SS)PB4_44") (pintype "bidirectional"))
    )
    (net (code "76") (name "unconnected-(IC1-(T1)PB1-Pad41)") (class "Default")
      (node (ref "IC1") (pin "41") (pinfunction "(T1)PB1_41") (pintype "bidirectional"))
    )
    (net (code "77") (name "unconnected-(IC1-(TCK)PC2-Pad21)") (class "Default")
      (node (ref "IC1") (pin "21") (pinfunction "(TCK)PC2_21") (pintype "bidirectional"))
    )
    (net (code "78") (name "unconnected-(IC1-(TDI)PC5-Pad24)") (class "Default")
      (node (ref "IC1") (pin "24") (pinfunction "(TDI)PC5_24") (pintype "bidirectional"))
    )
    (net (code "79") (name "unconnected-(IC1-(TDO)PC4-Pad23)") (class "Default")
      (node (ref "IC1") (pin "23") (pinfunction "(TDO)PC4_23") (pintype "bidirectional"))
    )
    (net (code "80") (name "unconnected-(IC1-(TMS)PC3-Pad22)") (class "Default")
      (node (ref "IC1") (pin "22") (pinfunction "(TMS)PC3_22") (pintype "bidirectional"))
    )
    (net (code "81") (name "unconnected-(IC1-(TOSC1)PC6-Pad25)") (class "Default")
      (node (ref "IC1") (pin "25") (pinfunction "(TOSC1)PC6_25") (pintype "bidirectional"))
    )
    (net (code "82") (name "unconnected-(IC1-(TOSC2)PC7-Pad26)") (class "Default")
      (node (ref "IC1") (pin "26") (pinfunction "(TOSC2)PC7_26") (pintype "bidirectional"))
    )
    (net (code "83") (name "unconnected-(IC1-AREF-Pad29)") (class "Default")
      (node (ref "IC1") (pin "29") (pinfunction "AREF_29") (pintype "passive"))
    )
    (net (code "84") (name "unconnected-(IC1-PC0(SCL)-Pad19)") (class "Default")
      (node (ref "IC1") (pin "19") (pinfunction "PC0(SCL)_19") (pintype "bidirectional"))
    )
    (net (code "85") (name "unconnected-(IC1-PC1(SDA)-Pad20)") (class "Default")
      (node (ref "IC1") (pin "20") (pinfunction "PC1(SDA)_20") (pintype "bidirectional"))
    )
    (net (code "86") (name "unconnected-(IC2-CBUS2-Pad13)") (class "Default")
      (node (ref "IC2") (pin "13") (pinfunction "CBUS2_13") (pintype "bidirectional"))
    )
    (net (code "87") (name "unconnected-(IC2-CBUS3-Pad14)") (class "Default")
      (node (ref "IC2") (pin "14") (pinfunction "CBUS3_14") (pintype "bidirectional"))
    )
    (net (code "88") (name "unconnected-(IC2-CBUS4-Pad12)") (class "Default")
      (node (ref "IC2") (pin "12") (pinfunction "CBUS4_12") (pintype "bidirectional"))
    )
    (net (code "89") (name "unconnected-(IC2-OSCI-Pad27)") (class "Default")
      (node (ref "IC2") (pin "27") (pinfunction "OSCI_27") (pintype "input"))
    )
    (net (code "90") (name "unconnected-(IC2-OSCO-Pad28)") (class "Default")
      (node (ref "IC2") (pin "28") (pinfunction "OSCO_28") (pintype "output"))
    )
    (net (code "91") (name "unconnected-(IC2-~{CTS}-Pad11)") (class "Default")
      (node (ref "IC2") (pin "11") (pinfunction "~{CTS}_11") (pintype "input"))
    )
    (net (code "92") (name "unconnected-(IC2-~{DCD}-Pad10)") (class "Default")
      (node (ref "IC2") (pin "10") (pinfunction "~{DCD}_10") (pintype "input"))
    )
    (net (code "93") (name "unconnected-(IC2-~{DSR}-Pad9)") (class "Default")
      (node (ref "IC2") (pin "9") (pinfunction "~{DSR}_9") (pintype "input"))
    )
    (net (code "94") (name "unconnected-(IC2-~{DTR}-Pad2)") (class "Default")
      (node (ref "IC2") (pin "2") (pinfunction "~{DTR}_2") (pintype "output"))
    )
    (net (code "95") (name "unconnected-(IC2-~{RESET}-Pad19)") (class "Default")
      (node (ref "IC2") (pin "19") (pinfunction "~{RESET}_19") (pintype "input"))
    )
    (net (code "96") (name "unconnected-(IC2-~{RI}-Pad6)") (class "Default")
      (node (ref "IC2") (pin "6") (pinfunction "~{RI}_6") (pintype "input"))
    )
    (net (code "97") (name "unconnected-(IC2-~{RTS}-Pad3)") (class "Default")
      (node (ref "IC2") (pin "3") (pinfunction "~{RTS}_3") (pintype "output"))
    )
    (net (code "98") (name "unconnected-(T2-PadA1)") (class "Default")
      (node (ref "T2") (pin "A1") (pinfunction "A1_A1") (pintype "bidirectional"))
    )
    (net (code "99") (name "unconnected-(T3-PadA1)") (class "Default")
      (node (ref "T3") (pin "A1") (pinfunction "A1_A1") (pintype "bidirectional"))
    )
    (net (code "100") (name "unconnected-(U$1-AREF-Pad62)") (class "Default")
      (node (ref "U$1") (pin "62") (pinfunction "AREF_62") (pintype "input"))
    )
    (net (code "101") (name "unconnected-(U$1-DNC-Pad1)") (class "Default")
      (node (ref "U$1") (pin "1") (pinfunction "DNC_1") (pintype "input"))
    )
    (net (code "102") (name "unconnected-(U$1-ICP1{slash}PD0-Pad25)") (class "Default")
      (node (ref "U$1") (pin "25") (pinfunction "ICP1/PD0_25") (pintype "bidirectional"))
    )
    (net (code "103") (name "unconnected-(U$1-OC1A{slash}PCINT13{slash}PB5-Pad15)") (class "Default")
      (node (ref "U$1") (pin "15") (pinfunction "OC1A/PCINT13/PB5_15") (pintype "bidirectional"))
    )
    (net (code "104") (name "unconnected-(U$1-OC1B{slash}PCINT14{slash}PB6-Pad16)") (class "Default")
      (node (ref "U$1") (pin "16") (pinfunction "OC1B/PCINT14/PB6_16") (pintype "bidirectional"))
    )
    (net (code "105") (name "unconnected-(U$1-OC2A{slash}PCINT15{slash}PB7-Pad17)") (class "Default")
      (node (ref "U$1") (pin "17") (pinfunction "OC2A/PCINT15/PB7_17") (pintype "bidirectional"))
    )
    (net (code "106") (name "unconnected-(U$1-PC0-Pad35)") (class "Default")
      (node (ref "U$1") (pin "35") (pinfunction "PC0_35") (pintype "bidirectional"))
    )
    (net (code "107") (name "unconnected-(U$1-PC1-Pad36)") (class "Default")
      (node (ref "U$1") (pin "36") (pinfunction "PC1_36") (pintype "bidirectional"))
    )
    (net (code "108") (name "unconnected-(U$1-PC2-Pad37)") (class "Default")
      (node (ref "U$1") (pin "37") (pinfunction "PC2_37") (pintype "bidirectional"))
    )
    (net (code "109") (name "unconnected-(U$1-PD2-Pad27)") (class "Default")
      (node (ref "U$1") (pin "27") (pinfunction "PD2_27") (pintype "bidirectional"))
    )
    (net (code "110") (name "unconnected-(U$1-PD3-Pad28)") (class "Default")
      (node (ref "U$1") (pin "28") (pinfunction "PD3_28") (pintype "bidirectional"))
    )
    (net (code "111") (name "unconnected-(U$1-PD4-Pad29)") (class "Default")
      (node (ref "U$1") (pin "29") (pinfunction "PD4_29") (pintype "bidirectional"))
    )
    (net (code "112") (name "unconnected-(U$1-PD5-Pad30)") (class "Default")
      (node (ref "U$1") (pin "30") (pinfunction "PD5_30") (pintype "bidirectional"))
    )
    (net (code "113") (name "unconnected-(U$1-PD6-Pad31)") (class "Default")
      (node (ref "U$1") (pin "31") (pinfunction "PD6_31") (pintype "bidirectional"))
    )
    (net (code "114") (name "unconnected-(U$1-PG0-Pad33)") (class "Default")
      (node (ref "U$1") (pin "33") (pinfunction "PG0_33") (pintype "bidirectional"))
    )
    (net (code "115") (name "unconnected-(U$1-PG1-Pad34)") (class "Default")
      (node (ref "U$1") (pin "34") (pinfunction "PG1_34") (pintype "bidirectional"))
    )
    (net (code "116") (name "unconnected-(U$1-PG2-Pad43)") (class "Default")
      (node (ref "U$1") (pin "43") (pinfunction "PG2_43") (pintype "bidirectional"))
    )
    (net (code "117") (name "unconnected-(U$1-T0{slash}PG4-Pad19)") (class "Default")
      (node (ref "U$1") (pin "19") (pinfunction "T0/PG4_19") (pintype "bidirectional"))
    )
    (net (code "118") (name "unconnected-(U$1-T1{slash}PG3-Pad18)") (class "Default")
      (node (ref "U$1") (pin "18") (pinfunction "T1/PG3_18") (pintype "bidirectional"))
    )
    (net (code "119") (name "unconnected-(X2-Pad2)") (class "Default")
      (node (ref "X2") (pin "2") (pinfunction "2_2") (pintype "passive"))
    )
    (net (code "120") (name "unconnected-(X2-Pad6)") (class "Default")
      (node (ref "X2") (pin "6") (pinfunction "6_6") (pintype "passive"))
    )
    (net (code "121") (name "unconnected-(X3AA-1-Pad33)") (class "Default")
      (node (ref "X3") (pin "33") (pinfunction "1_33") (pintype "passive"))
    )
    (net (code "122") (name "unconnected-(X3AB-1-Pad34)") (class "Default")
      (node (ref "X3") (pin "34") (pinfunction "1_34") (pintype "passive"))
    )
    (net (code "123") (name "unconnected-(X3AH-1-Pad4)") (class "Default")
      (node (ref "X3") (pin "4") (pinfunction "1_4") (pintype "passive"))
    )
    (net (code "124") (name "unconnected-(X3S-1-Pad26)") (class "Default")
      (node (ref "X3") (pin "26") (pinfunction "1_26") (pintype "passive"))
    )
    (net (code "125") (name "unconnected-(X3T-1-Pad27)") (class "Default")
      (node (ref "X3") (pin "27") (pinfunction "1_27") (pintype "passive"))
    )
    (net (code "126") (name "unconnected-(X3X-1-Pad30)") (class "Default")
      (node (ref "X3") (pin "30") (pinfunction "1_30") (pintype "passive"))
    )
    (net (code "127") (name "unconnected-(X3Y-1-Pad31)") (class "Default")
      (node (ref "X3") (pin "31") (pinfunction "1_31") (pintype "passive"))
    )
    (net (code "128") (name "unconnected-(X3Z-1-Pad32)") (class "Default")
      (node (ref "X3") (pin "32") (pinfunction "1_32") (pintype "passive"))
    )
  )
)
